# WiFi_MBUS_Reader.net
KiCad netlist of a schematic drawn in EAGLE
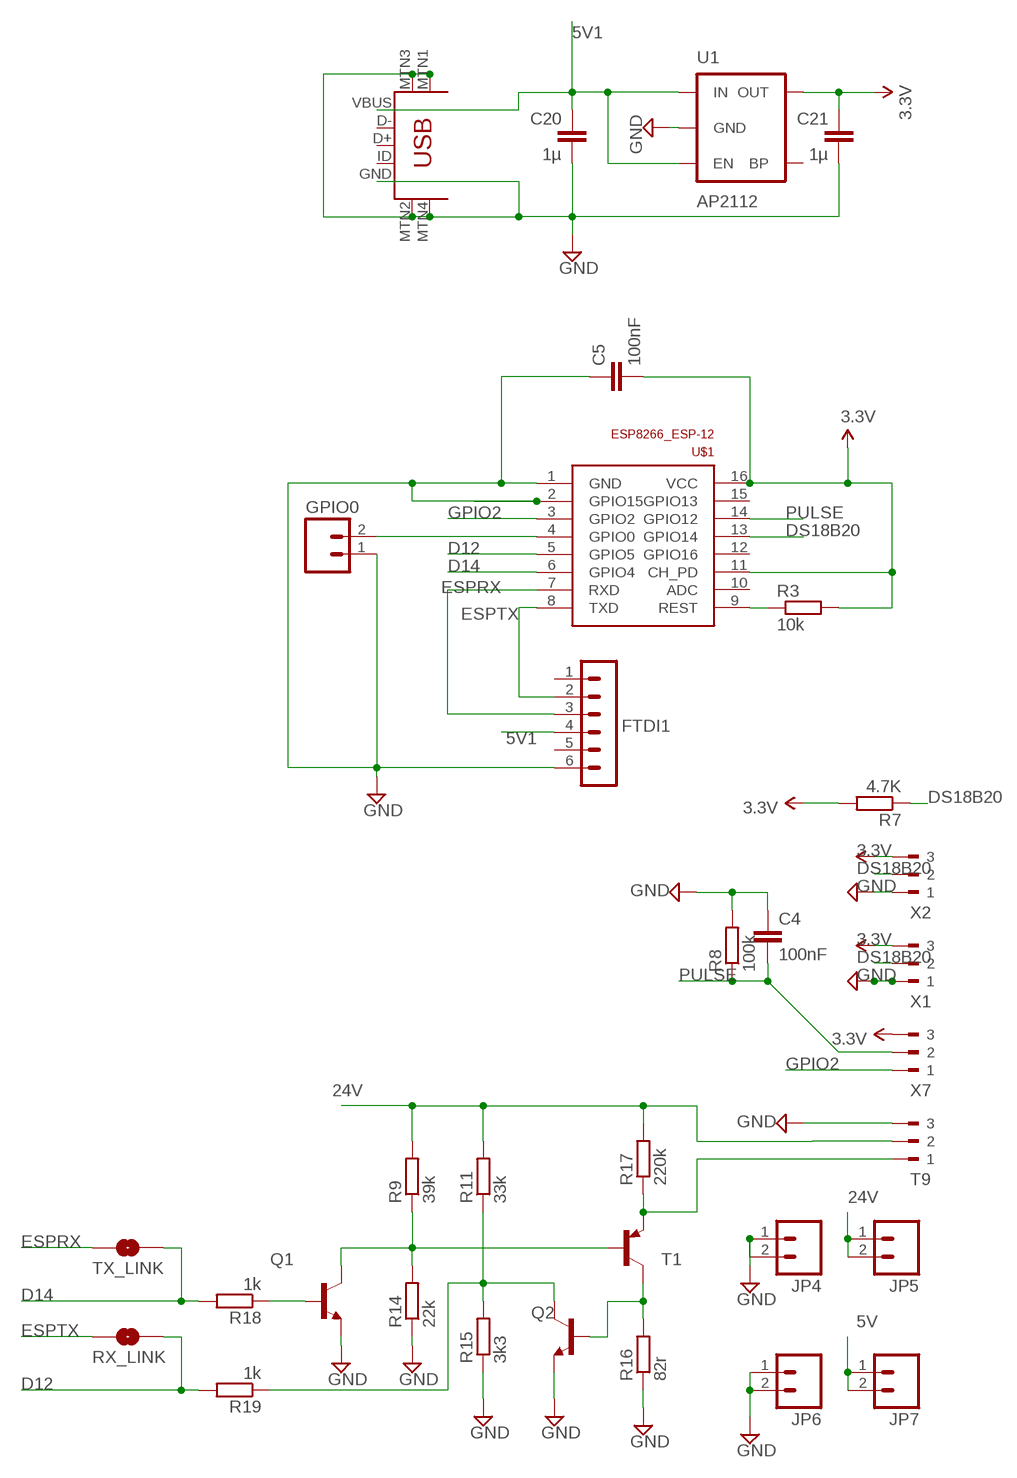
[diagram p0: schematic, sheet 1]

(export (version "E")
  (design (tool "Eeschema 10.0.6"))
  (components
    (comp (ref "C4")
      (value "100nF")
      (footprint "eagle-import:C0603")
      (libsource (lib "eagle-import") (part "C-EUC0603"))
    )
    (comp (ref "C5")
      (value "100nF")
      (footprint "eagle-import:C0603")
      (libsource (lib "eagle-import") (part "C-EUC0603"))
    )
    (comp (ref "C20")
      (value "1µ")
      (footprint "eagle-import:C0603")
      (libsource (lib "eagle-import") (part "C-EUC0603"))
    )
    (comp (ref "C21")
      (value "1µ")
      (footprint "eagle-import:C0603")
      (libsource (lib "eagle-import") (part "C-EUC0603"))
    )
    (comp (ref "FTDI1")
      (value "FTDI")
      (footprint "eagle-import:MA06-1")
      (libsource (lib "eagle-import") (part "MA06-1"))
    )
    (comp (ref "GPIO0")
      (value "M02PTH")
      (footprint "eagle-import:1X02")
      (libsource (lib "eagle-import") (part "M02PTH"))
    )
    (comp (ref "JP4")
      (value "M02PTH")
      (footprint "eagle-import:1X02")
      (libsource (lib "eagle-import") (part "M02PTH"))
    )
    (comp (ref "JP5")
      (value "M02PTH")
      (footprint "eagle-import:1X02")
      (libsource (lib "eagle-import") (part "M02PTH"))
    )
    (comp (ref "JP6")
      (value "M02PTH")
      (footprint "eagle-import:1X02")
      (libsource (lib "eagle-import") (part "M02PTH"))
    )
    (comp (ref "JP7")
      (value "M02PTH")
      (footprint "eagle-import:1X02")
      (libsource (lib "eagle-import") (part "M02PTH"))
    )
    (comp (ref "Q1")
      (value "BC808-NPN-SOT23-BEC")
      (footprint "eagle-import:SOT23-BEC")
      (libsource (lib "eagle-import") (part "-NPN-SOT23-BECBC808"))
    )
    (comp (ref "Q2")
      (value "BC808-NPN-SOT23-BEC")
      (footprint "eagle-import:SOT23-BEC")
      (libsource (lib "eagle-import") (part "-NPN-SOT23-BECBC808"))
    )
    (comp (ref "R3")
      (value "10k")
      (footprint "eagle-import:R0603")
      (libsource (lib "eagle-import") (part "R-EU_R0603"))
    )
    (comp (ref "R7")
      (value "4.7K")
      (footprint "eagle-import:R0603")
      (libsource (lib "eagle-import") (part "R-EU_R0603"))
    )
    (comp (ref "R8")
      (value "100k")
      (footprint "eagle-import:R0603")
      (libsource (lib "eagle-import") (part "R-EU_R0603"))
    )
    (comp (ref "R9")
      (value "39k")
      (footprint "eagle-import:R0603")
      (libsource (lib "eagle-import") (part "R-EU_R0603"))
    )
    (comp (ref "R11")
      (value "33k")
      (footprint "eagle-import:R0603")
      (libsource (lib "eagle-import") (part "R-EU_R0603"))
    )
    (comp (ref "R14")
      (value "22k")
      (footprint "eagle-import:R0603")
      (libsource (lib "eagle-import") (part "R-EU_R0603"))
    )
    (comp (ref "R15")
      (value "3k3")
      (footprint "eagle-import:R0603")
      (libsource (lib "eagle-import") (part "R-EU_R0603"))
    )
    (comp (ref "R16")
      (value "82r")
      (footprint "eagle-import:R0603")
      (libsource (lib "eagle-import") (part "R-EU_R0603"))
    )
    (comp (ref "R17")
      (value "220k")
      (footprint "eagle-import:R0603")
      (libsource (lib "eagle-import") (part "R-EU_R0603"))
    )
    (comp (ref "R18")
      (value "1k")
      (footprint "eagle-import:R0603")
      (libsource (lib "eagle-import") (part "R-EU_R0603"))
    )
    (comp (ref "R19")
      (value "1k")
      (footprint "eagle-import:R0603")
      (libsource (lib "eagle-import") (part "R-EU_R0603"))
    )
    (comp (ref "RX_LINK")
      (value "SOLDERJUMPERNO")
      (footprint "eagle-import:SJ_2S-NO")
      (libsource (lib "eagle-import") (part "SOLDERJUMPERNO"))
    )
    (comp (ref "T1")
      (value "BC807-16-PNP-SOT23-BEC")
      (footprint "eagle-import:SOT23-BEC")
      (libsource (lib "eagle-import") (part "-PNP-SOT23-BECBC807-16"))
    )
    (comp (ref "T9")
      (value "180-3")
      (footprint "eagle-import:180-3")
      (libsource (lib "eagle-import") (part "180-3"))
    )
    (comp (ref "TX_LINK")
      (value "SOLDERJUMPERNO")
      (footprint "eagle-import:SJ_2S-NO")
      (libsource (lib "eagle-import") (part "SOLDERJUMPERNO"))
    )
    (comp (ref "U$1")
      (value "ESP8266_ESP-12")
      (footprint "eagle-import:ESP8266-ESP12")
      (libsource (lib "eagle-import") (part "ESP8266_ESP-12"))
    )
    (comp (ref "U$10")
      (value "USB-MINIB-5PIN")
      (footprint "eagle-import:USB-MINIB-CISECO")
      (libsource (lib "eagle-import") (part "USB-MINIB-5PIN"))
    )
    (comp (ref "U1")
      (value "AP2112")
      (footprint "eagle-import:SOT23-5")
      (libsource (lib "eagle-import") (part "V_REG_LDOSMD"))
    )
    (comp (ref "X1")
      (value "180-3")
      (footprint "eagle-import:180-3")
      (libsource (lib "eagle-import") (part "180-3"))
    )
    (comp (ref "X2")
      (value "180-3")
      (footprint "eagle-import:180-3")
      (libsource (lib "eagle-import") (part "180-3"))
    )
    (comp (ref "X7")
      (value "180-3")
      (footprint "eagle-import:180-3")
      (libsource (lib "eagle-import") (part "180-3"))
    )
  )
  (nets
    (net (code "1") (name "/5V") (class "Default")
      (node (ref "JP7") (pin "1") (pinfunction "1_1") (pintype "passive"))
      (node (ref "JP7") (pin "2") (pinfunction "2_2") (pintype "passive"))
    )
    (net (code "2") (name "/5V1") (class "Default")
      (node (ref "C20") (pin "1") (pinfunction "1_1") (pintype "passive"))
      (node (ref "FTDI1") (pin "4") (pinfunction "4_4") (pintype "passive"))
      (node (ref "U$10") (pin "VBUS") (pinfunction "VBUS_VBUS") (pintype "bidirectional"))
      (node (ref "U1") (pin "1") (pinfunction "IN_1") (pintype "input"))
      (node (ref "U1") (pin "3") (pinfunction "EN_3") (pintype "input"))
    )
    (net (code "3") (name "/24V") (class "Default")
      (node (ref "JP5") (pin "1") (pinfunction "1_1") (pintype "passive"))
      (node (ref "JP5") (pin "2") (pinfunction "2_2") (pintype "passive"))
      (node (ref "R11") (pin "2") (pinfunction "2_2") (pintype "passive"))
      (node (ref "R17") (pin "2") (pinfunction "2_2") (pintype "passive"))
      (node (ref "R9") (pin "2") (pinfunction "2_2") (pintype "passive"))
      (node (ref "T9") (pin "2") (pinfunction "2_2") (pintype "passive"))
    )
    (net (code "4") (name "/D12") (class "Default")
      (node (ref "R19") (pin "2") (pinfunction "2_2") (pintype "passive"))
      (node (ref "RX_LINK") (pin "2") (pinfunction "2_2") (pintype "passive"))
      (node (ref "U$1") (pin "5") (pinfunction "GPIO5_5") (pintype "bidirectional"))
    )
    (net (code "5") (name "/D14") (class "Default")
      (node (ref "R18") (pin "2") (pinfunction "2_2") (pintype "passive"))
      (node (ref "TX_LINK") (pin "2") (pinfunction "2_2") (pintype "passive"))
      (node (ref "U$1") (pin "6") (pinfunction "GPIO4_6") (pintype "bidirectional"))
    )
    (net (code "6") (name "/DS18B20") (class "Default")
      (node (ref "R7") (pin "1") (pinfunction "1_1") (pintype "passive"))
      (node (ref "U$1") (pin "13") (pinfunction "GPIO14_13") (pintype "bidirectional"))
      (node (ref "X1") (pin "2") (pinfunction "2_2") (pintype "passive"))
      (node (ref "X2") (pin "2") (pinfunction "2_2") (pintype "passive"))
    )
    (net (code "7") (name "/ESPRX") (class "Default")
      (node (ref "FTDI1") (pin "3") (pinfunction "3_3") (pintype "passive"))
      (node (ref "TX_LINK") (pin "1") (pinfunction "1_1") (pintype "passive"))
      (node (ref "U$1") (pin "7") (pinfunction "RXD_7") (pintype "bidirectional"))
    )
    (net (code "8") (name "/ESPTX") (class "Default")
      (node (ref "FTDI1") (pin "2") (pinfunction "2_2") (pintype "passive"))
      (node (ref "RX_LINK") (pin "1") (pinfunction "1_1") (pintype "passive"))
      (node (ref "U$1") (pin "8") (pinfunction "TXD_8") (pintype "bidirectional"))
    )
    (net (code "9") (name "/GPIO2") (class "Default")
      (node (ref "U$1") (pin "3") (pinfunction "GPIO2_3") (pintype "bidirectional"))
      (node (ref "X7") (pin "1") (pinfunction "1_1") (pintype "passive"))
    )
    (net (code "10") (name "/PULSE") (class "Default")
      (node (ref "C4") (pin "2") (pinfunction "2_2") (pintype "passive"))
      (node (ref "R8") (pin "1") (pinfunction "1_1") (pintype "passive"))
      (node (ref "U$1") (pin "14") (pinfunction "GPIO12_14") (pintype "bidirectional"))
      (node (ref "X7") (pin "2") (pinfunction "2_2") (pintype "passive"))
    )
    (net (code "11") (name "3.3V") (class "Default")
      (node (ref "C21") (pin "1") (pinfunction "1_1") (pintype "passive"))
      (node (ref "C5") (pin "2") (pinfunction "2_2") (pintype "passive"))
      (node (ref "R3") (pin "2") (pinfunction "2_2") (pintype "passive"))
      (node (ref "R7") (pin "2") (pinfunction "2_2") (pintype "passive"))
      (node (ref "U$1") (pin "11") (pinfunction "CH_PD_11") (pintype "bidirectional"))
      (node (ref "U$1") (pin "16") (pinfunction "VCC_16") (pintype "bidirectional"))
      (node (ref "U1") (pin "5") (pinfunction "OUT_5") (pintype "passive"))
      (node (ref "X1") (pin "3") (pinfunction "3_3") (pintype "passive"))
      (node (ref "X2") (pin "3") (pinfunction "3_3") (pintype "passive"))
      (node (ref "X7") (pin "3") (pinfunction "3_3") (pintype "passive"))
    )
    (net (code "12") (name "GND") (class "Default")
      (node (ref "C20") (pin "2") (pinfunction "2_2") (pintype "passive"))
      (node (ref "C21") (pin "2") (pinfunction "2_2") (pintype "passive"))
      (node (ref "C4") (pin "1") (pinfunction "1_1") (pintype "passive"))
      (node (ref "C5") (pin "1") (pinfunction "1_1") (pintype "passive"))
      (node (ref "FTDI1") (pin "6") (pinfunction "6_6") (pintype "passive"))
      (node (ref "GPIO0") (pin "1") (pinfunction "1_1") (pintype "passive"))
      (node (ref "JP4") (pin "1") (pinfunction "1_1") (pintype "passive"))
      (node (ref "JP4") (pin "2") (pinfunction "2_2") (pintype "passive"))
      (node (ref "JP6") (pin "1") (pinfunction "1_1") (pintype "passive"))
      (node (ref "JP6") (pin "2") (pinfunction "2_2") (pintype "passive"))
      (node (ref "Q1") (pin "E") (pinfunction "E_E") (pintype "passive"))
      (node (ref "Q2") (pin "E") (pinfunction "E_E") (pintype "passive"))
      (node (ref "R14") (pin "1") (pinfunction "1_1") (pintype "passive"))
      (node (ref "R15") (pin "1") (pinfunction "1_1") (pintype "passive"))
      (node (ref "R16") (pin "1") (pinfunction "1_1") (pintype "passive"))
      (node (ref "R8") (pin "2") (pinfunction "2_2") (pintype "passive"))
      (node (ref "T9") (pin "3") (pinfunction "3_3") (pintype "passive"))
      (node (ref "U$1") (pin "1") (pinfunction "GND_1") (pintype "bidirectional"))
      (node (ref "U$1") (pin "2") (pinfunction "GPIO15_2") (pintype "bidirectional"))
      (node (ref "U$10") (pin "GND") (pinfunction "GND_GND") (pintype "bidirectional"))
      (node (ref "U$10") (pin "MTN1") (pinfunction "MTN2_MTN1") (pintype "bidirectional"))
      (node (ref "U$10") (pin "MTN2") (pinfunction "MTN3_MTN2") (pintype "bidirectional"))
      (node (ref "U$10") (pin "MTN3") (pinfunction "MTN1_MTN3") (pintype "bidirectional"))
      (node (ref "U$10") (pin "MTN4") (pinfunction "MTN4_MTN4") (pintype "bidirectional"))
      (node (ref "U1") (pin "2") (pinfunction "GND_2") (pintype "input"))
      (node (ref "X1") (pin "1") (pinfunction "1_1") (pintype "passive"))
      (node (ref "X2") (pin "1") (pinfunction "1_1") (pintype "passive"))
    )
    (net (code "13") (name "Net-(Q1-PadB)") (class "Default")
      (node (ref "Q1") (pin "B") (pinfunction "B_B") (pintype "passive"))
      (node (ref "R18") (pin "1") (pinfunction "1_1") (pintype "passive"))
    )
    (net (code "14") (name "Net-(Q1-PadC)") (class "Default")
      (node (ref "Q1") (pin "C") (pinfunction "C_C") (pintype "passive"))
      (node (ref "R14") (pin "2") (pinfunction "2_2") (pintype "passive"))
      (node (ref "R9") (pin "1") (pinfunction "1_1") (pintype "passive"))
      (node (ref "T1") (pin "B") (pinfunction "B_B") (pintype "passive"))
    )
    (net (code "15") (name "Net-(Q2-PadB)") (class "Default")
      (node (ref "Q2") (pin "B") (pinfunction "B_B") (pintype "passive"))
      (node (ref "R16") (pin "2") (pinfunction "2_2") (pintype "passive"))
      (node (ref "T1") (pin "C") (pinfunction "C_C") (pintype "passive"))
    )
    (net (code "16") (name "Net-(Q2-PadC)") (class "Default")
      (node (ref "Q2") (pin "C") (pinfunction "C_C") (pintype "passive"))
      (node (ref "R11") (pin "1") (pinfunction "1_1") (pintype "passive"))
      (node (ref "R15") (pin "2") (pinfunction "2_2") (pintype "passive"))
      (node (ref "R19") (pin "1") (pinfunction "1_1") (pintype "passive"))
    )
    (net (code "17") (name "Net-(R17-Pad1)") (class "Default")
      (node (ref "R17") (pin "1") (pinfunction "1_1") (pintype "passive"))
      (node (ref "T1") (pin "E") (pinfunction "E_E") (pintype "passive"))
      (node (ref "T9") (pin "1") (pinfunction "1_1") (pintype "passive"))
    )
    (net (code "18") (name "Net-(U$1-GPIO0)") (class "Default")
      (node (ref "GPIO0") (pin "2") (pinfunction "2_2") (pintype "passive"))
      (node (ref "U$1") (pin "4") (pinfunction "GPIO0_4") (pintype "bidirectional"))
    )
    (net (code "19") (name "Net-(U$1-REST)") (class "Default")
      (node (ref "R3") (pin "1") (pinfunction "1_1") (pintype "passive"))
      (node (ref "U$1") (pin "9") (pinfunction "REST_9") (pintype "bidirectional"))
    )
    (net (code "20") (name "unconnected-(FTDI1-Pad1)") (class "Default")
      (node (ref "FTDI1") (pin "1") (pinfunction "1_1") (pintype "passive"))
    )
    (net (code "21") (name "unconnected-(FTDI1-Pad5)") (class "Default")
      (node (ref "FTDI1") (pin "5") (pinfunction "5_5") (pintype "passive"))
    )
    (net (code "22") (name "unconnected-(U$1-ADC-Pad10)") (class "Default")
      (node (ref "U$1") (pin "10") (pinfunction "ADC_10") (pintype "bidirectional"))
    )
    (net (code "23") (name "unconnected-(U$1-GPIO13-Pad15)") (class "Default")
      (node (ref "U$1") (pin "15") (pinfunction "GPIO13_15") (pintype "bidirectional"))
    )
    (net (code "24") (name "unconnected-(U$1-GPIO16-Pad12)") (class "Default")
      (node (ref "U$1") (pin "12") (pinfunction "GPIO16_12") (pintype "bidirectional"))
    )
    (net (code "25") (name "unconnected-(U$10-PadD+)") (class "Default")
      (node (ref "U$10") (pin "D+") (pinfunction "D+_D+") (pintype "bidirectional"))
    )
    (net (code "26") (name "unconnected-(U$10-PadD-)") (class "Default")
      (node (ref "U$10") (pin "D-") (pinfunction "D-_D-") (pintype "bidirectional"))
    )
    (net (code "27") (name "unconnected-(U$10-PadID)") (class "Default")
      (node (ref "U$10") (pin "ID") (pinfunction "ID_ID") (pintype "bidirectional"))
    )
    (net (code "28") (name "unconnected-(U1-BP-Pad4)") (class "Default")
      (node (ref "U1") (pin "4") (pinfunction "BP_4") (pintype "input"))
    )
  )
)
